# CONNECTORS.net
KiCad netlist of a schematic drawn in Altium Designer
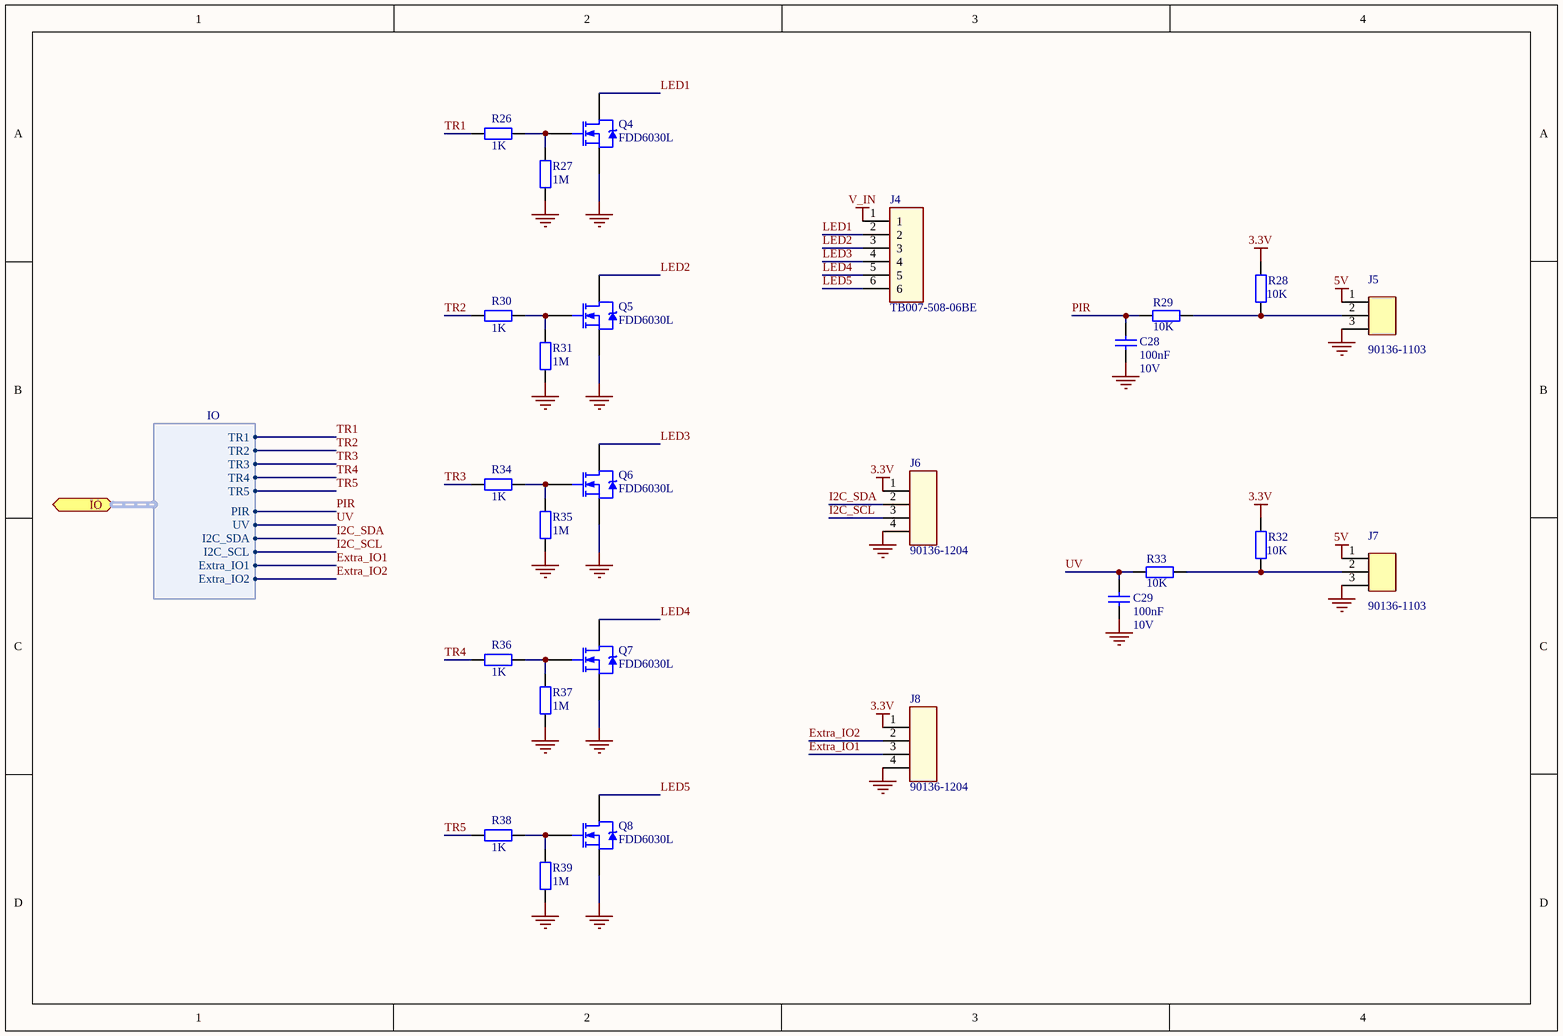
[diagram p0: CONNECTORS.SchDoc]

(export (version "E")
  (design (tool "Eeschema 10.0.6"))
  (components
    (comp (ref "C28")
      (value "Capacitor")
      (footprint "CAPC1608N")
      (fields
        (field (name "PART NUMBER") "CAP-000000005")
        (field (name "VALUE 1") "100nF")
        (field (name "VALUE 2") "10V")
      )
      (libsource (lib "ESP32-Relay-Module") (part "Capacitor"))
    )
    (comp (ref "C29")
      (value "Capacitor")
      (footprint "CAPC1608N")
      (fields
        (field (name "PART NUMBER") "CAP-000000005")
        (field (name "VALUE 1") "100nF")
        (field (name "VALUE 2") "10V")
      )
      (libsource (lib "ESP32-Relay-Module") (part "Capacitor"))
    )
    (comp (ref "J4")
      (value "TB007-508-06BE")
      (footprint "HDR1X6")
      (fields (field (name "PART NUMBER") "CON-000000007"))
      (libsource (lib "ESP32-Relay-Module") (part "Header 1X6"))
    )
    (comp (ref "J5")
      (value "90136-1103")
      (footprint "HDR1X3")
      (fields (field (name "PART NUMBER") "CON-000000003"))
      (libsource (lib "ESP32-Relay-Module") (part "Header 1X3"))
    )
    (comp (ref "J6")
      (value "90136-1204")
      (footprint "HDR1X4")
      (fields (field (name "PART NUMBER") "CON-000000004"))
      (libsource (lib "ESP32-Relay-Module") (part "Header 1X4"))
    )
    (comp (ref "J7")
      (value "90136-1103")
      (footprint "HDR1X3")
      (fields (field (name "PART NUMBER") "CON-000000003"))
      (libsource (lib "ESP32-Relay-Module") (part "Header 1X3"))
    )
    (comp (ref "J8")
      (value "90136-1204")
      (footprint "HDR1X4")
      (fields (field (name "PART NUMBER") "CON-000000004"))
      (libsource (lib "ESP32-Relay-Module") (part "Header 1X4"))
    )
    (comp (ref "Q4")
      (value "FDD6030L")
      (footprint "TO-252-3")
      (fields (field (name "PART NUMBER") "TRM-000000001"))
      (libsource (lib "ESP32-Relay-Module") (part "MOSFET-N-1"))
    )
    (comp (ref "Q5")
      (value "FDD6030L")
      (footprint "TO-252-3")
      (fields (field (name "PART NUMBER") "TRM-000000001"))
      (libsource (lib "ESP32-Relay-Module") (part "MOSFET-N-1"))
    )
    (comp (ref "Q6")
      (value "FDD6030L")
      (footprint "TO-252-3")
      (fields (field (name "PART NUMBER") "TRM-000000001"))
      (libsource (lib "ESP32-Relay-Module") (part "MOSFET-N-1"))
    )
    (comp (ref "Q7")
      (value "FDD6030L")
      (footprint "TO-252-3")
      (fields (field (name "PART NUMBER") "TRM-000000001"))
      (libsource (lib "ESP32-Relay-Module") (part "MOSFET-N-1"))
    )
    (comp (ref "Q8")
      (value "FDD6030L")
      (footprint "TO-252-3")
      (fields (field (name "PART NUMBER") "TRM-000000001"))
      (libsource (lib "ESP32-Relay-Module") (part "MOSFET-N-1"))
    )
    (comp (ref "R26")
      (value "Resistor")
      (footprint "RESC1608N")
      (fields (field (name "PART NUMBER") "RES-000000006") (field (name "VALUE 1") "1K"))
      (libsource (lib "") (part "Resistor_1"))
    )
    (comp (ref "R27")
      (value "Resistor")
      (footprint "RESC1608N")
      (fields (field (name "PART NUMBER") "RES-000000010") (field (name "VALUE 1") "1M"))
      (libsource (lib "ESP32-Relay-Module") (part "Resistor"))
    )
    (comp (ref "R28")
      (value "Resistor")
      (footprint "RESC1608N")
      (fields (field (name "PART NUMBER") "RES-000000001") (field (name "VALUE 1") "10K"))
      (libsource (lib "ESP32-Relay-Module") (part "Resistor"))
    )
    (comp (ref "R29")
      (value "Resistor")
      (footprint "RESC1608N")
      (fields (field (name "PART NUMBER") "RES-000000001") (field (name "VALUE 1") "10K"))
      (libsource (lib "") (part "Resistor_2"))
    )
    (comp (ref "R30")
      (value "Resistor")
      (footprint "RESC1608N")
      (fields (field (name "PART NUMBER") "RES-000000006") (field (name "VALUE 1") "1K"))
      (libsource (lib "") (part "Resistor_1"))
    )
    (comp (ref "R31")
      (value "Resistor")
      (footprint "RESC1608N")
      (fields (field (name "PART NUMBER") "RES-000000010") (field (name "VALUE 1") "1M"))
      (libsource (lib "ESP32-Relay-Module") (part "Resistor"))
    )
    (comp (ref "R32")
      (value "Resistor")
      (footprint "RESC1608N")
      (fields (field (name "PART NUMBER") "RES-000000001") (field (name "VALUE 1") "10K"))
      (libsource (lib "ESP32-Relay-Module") (part "Resistor"))
    )
    (comp (ref "R33")
      (value "Resistor")
      (footprint "RESC1608N")
      (fields (field (name "PART NUMBER") "RES-000000001") (field (name "VALUE 1") "10K"))
      (libsource (lib "") (part "Resistor_2"))
    )
    (comp (ref "R34")
      (value "Resistor")
      (footprint "RESC1608N")
      (fields (field (name "PART NUMBER") "RES-000000006") (field (name "VALUE 1") "1K"))
      (libsource (lib "") (part "Resistor_1"))
    )
    (comp (ref "R35")
      (value "Resistor")
      (footprint "RESC1608N")
      (fields (field (name "PART NUMBER") "RES-000000010") (field (name "VALUE 1") "1M"))
      (libsource (lib "ESP32-Relay-Module") (part "Resistor"))
    )
    (comp (ref "R36")
      (value "Resistor")
      (footprint "RESC1608N")
      (fields (field (name "PART NUMBER") "RES-000000006") (field (name "VALUE 1") "1K"))
      (libsource (lib "") (part "Resistor_1"))
    )
    (comp (ref "R37")
      (value "Resistor")
      (footprint "RESC1608N")
      (fields (field (name "PART NUMBER") "RES-000000010") (field (name "VALUE 1") "1M"))
      (libsource (lib "ESP32-Relay-Module") (part "Resistor"))
    )
    (comp (ref "R38")
      (value "Resistor")
      (footprint "RESC1608N")
      (fields (field (name "PART NUMBER") "RES-000000006") (field (name "VALUE 1") "1K"))
      (libsource (lib "") (part "Resistor_1"))
    )
    (comp (ref "R39")
      (value "Resistor")
      (footprint "RESC1608N")
      (fields (field (name "PART NUMBER") "RES-000000010") (field (name "VALUE 1") "1M"))
      (libsource (lib "ESP32-Relay-Module") (part "Resistor"))
    )
  )
  (nets
    (net (code "2") (name "/Extra_IO1") (class "Default")
      (node (ref "J8") (pin "3") (pinfunction "3_3") (pintype "passive"))
    )
    (net (code "3") (name "/Extra_IO2") (class "Default")
      (node (ref "J8") (pin "2") (pinfunction "2_2") (pintype "passive"))
    )
    (net (code "4") (name "/I2C_SCL") (class "Default")
      (node (ref "J6") (pin "3") (pinfunction "3_3") (pintype "passive"))
    )
    (net (code "5") (name "/I2C_SDA") (class "Default")
      (node (ref "J6") (pin "2") (pinfunction "2_2") (pintype "passive"))
    )
    (net (code "6") (name "/LED1") (class "Default")
      (node (ref "J4") (pin "2") (pinfunction "2_2") (pintype "passive"))
      (node (ref "Q4") (pin "4") (pinfunction "D_4") (pintype "passive"))
    )
    (net (code "7") (name "/LED2") (class "Default")
      (node (ref "J4") (pin "3") (pinfunction "3_3") (pintype "passive"))
      (node (ref "Q5") (pin "4") (pinfunction "D_4") (pintype "passive"))
    )
    (net (code "8") (name "/LED3") (class "Default")
      (node (ref "J4") (pin "4") (pinfunction "4_4") (pintype "passive"))
      (node (ref "Q6") (pin "4") (pinfunction "D_4") (pintype "passive"))
    )
    (net (code "9") (name "/LED4") (class "Default")
      (node (ref "J4") (pin "5") (pinfunction "5_5") (pintype "passive"))
      (node (ref "Q7") (pin "4") (pinfunction "D_4") (pintype "passive"))
    )
    (net (code "10") (name "/LED5") (class "Default")
      (node (ref "J4") (pin "6") (pinfunction "6_6") (pintype "passive"))
      (node (ref "Q8") (pin "4") (pinfunction "D_4") (pintype "passive"))
    )
    (net (code "11") (name "/PIR") (class "Default")
      (node (ref "C28") (pin "2") (pinfunction "2_2") (pintype "passive"))
      (node (ref "R29") (pin "2") (pinfunction "2_2") (pintype "passive"))
    )
    (net (code "12") (name "/TR1") (class "Default")
      (node (ref "R26") (pin "1") (pinfunction "1_1") (pintype "passive"))
    )
    (net (code "13") (name "/TR2") (class "Default")
      (node (ref "R30") (pin "1") (pinfunction "1_1") (pintype "passive"))
    )
    (net (code "14") (name "/TR3") (class "Default")
      (node (ref "R34") (pin "1") (pinfunction "1_1") (pintype "passive"))
    )
    (net (code "15") (name "/TR4") (class "Default")
      (node (ref "R36") (pin "1") (pinfunction "1_1") (pintype "passive"))
    )
    (net (code "16") (name "/TR5") (class "Default")
      (node (ref "R38") (pin "1") (pinfunction "1_1") (pintype "passive"))
    )
    (net (code "17") (name "/UV") (class "Default")
      (node (ref "C29") (pin "2") (pinfunction "2_2") (pintype "passive"))
      (node (ref "R33") (pin "2") (pinfunction "2_2") (pintype "passive"))
    )
    (net (code "19") (name "3.3V") (class "Default")
      (node (ref "J6") (pin "1") (pinfunction "1_1") (pintype "passive"))
      (node (ref "J8") (pin "1") (pinfunction "1_1") (pintype "passive"))
      (node (ref "R28") (pin "2") (pinfunction "2_2") (pintype "passive"))
      (node (ref "R32") (pin "2") (pinfunction "2_2") (pintype "passive"))
    )
    (net (code "20") (name "5V") (class "Default")
      (node (ref "J5") (pin "1") (pinfunction "1_1") (pintype "passive"))
      (node (ref "J7") (pin "1") (pinfunction "1_1") (pintype "passive"))
    )
    (net (code "21") (name "GND") (class "Default")
      (node (ref "C28") (pin "1") (pinfunction "1_1") (pintype "passive"))
      (node (ref "C29") (pin "1") (pinfunction "1_1") (pintype "passive"))
      (node (ref "J5") (pin "3") (pinfunction "3_3") (pintype "passive"))
      (node (ref "J6") (pin "4") (pinfunction "4_4") (pintype "passive"))
      (node (ref "J7") (pin "3") (pinfunction "3_3") (pintype "passive"))
      (node (ref "J8") (pin "4") (pinfunction "4_4") (pintype "passive"))
      (node (ref "Q4") (pin "3") (pinfunction "S_3") (pintype "passive"))
      (node (ref "Q5") (pin "3") (pinfunction "S_3") (pintype "passive"))
      (node (ref "Q6") (pin "3") (pinfunction "S_3") (pintype "passive"))
      (node (ref "Q7") (pin "3") (pinfunction "S_3") (pintype "passive"))
      (node (ref "Q8") (pin "3") (pinfunction "S_3") (pintype "passive"))
      (node (ref "R27") (pin "1") (pinfunction "1_1") (pintype "passive"))
      (node (ref "R31") (pin "1") (pinfunction "1_1") (pintype "passive"))
      (node (ref "R35") (pin "1") (pinfunction "1_1") (pintype "passive"))
      (node (ref "R37") (pin "1") (pinfunction "1_1") (pintype "passive"))
      (node (ref "R39") (pin "1") (pinfunction "1_1") (pintype "passive"))
    )
    (net (code "22") (name "Net-(J5-Pad2)") (class "Default")
      (node (ref "J5") (pin "2") (pinfunction "2_2") (pintype "passive"))
      (node (ref "R28") (pin "1") (pinfunction "1_1") (pintype "passive"))
      (node (ref "R29") (pin "1") (pinfunction "1_1") (pintype "passive"))
    )
    (net (code "23") (name "Net-(J7-Pad2)") (class "Default")
      (node (ref "J7") (pin "2") (pinfunction "2_2") (pintype "passive"))
      (node (ref "R32") (pin "1") (pinfunction "1_1") (pintype "passive"))
      (node (ref "R33") (pin "1") (pinfunction "1_1") (pintype "passive"))
    )
    (net (code "24") (name "Net-(Q4-G)") (class "Default")
      (node (ref "Q4") (pin "1") (pinfunction "G_1") (pintype "passive"))
      (node (ref "R26") (pin "2") (pinfunction "2_2") (pintype "passive"))
      (node (ref "R27") (pin "2") (pinfunction "2_2") (pintype "passive"))
    )
    (net (code "25") (name "Net-(Q5-G)") (class "Default")
      (node (ref "Q5") (pin "1") (pinfunction "G_1") (pintype "passive"))
      (node (ref "R30") (pin "2") (pinfunction "2_2") (pintype "passive"))
      (node (ref "R31") (pin "2") (pinfunction "2_2") (pintype "passive"))
    )
    (net (code "26") (name "Net-(Q6-G)") (class "Default")
      (node (ref "Q6") (pin "1") (pinfunction "G_1") (pintype "passive"))
      (node (ref "R34") (pin "2") (pinfunction "2_2") (pintype "passive"))
      (node (ref "R35") (pin "2") (pinfunction "2_2") (pintype "passive"))
    )
    (net (code "27") (name "Net-(Q7-G)") (class "Default")
      (node (ref "Q7") (pin "1") (pinfunction "G_1") (pintype "passive"))
      (node (ref "R36") (pin "2") (pinfunction "2_2") (pintype "passive"))
      (node (ref "R37") (pin "2") (pinfunction "2_2") (pintype "passive"))
    )
    (net (code "28") (name "Net-(Q8-G)") (class "Default")
      (node (ref "Q8") (pin "1") (pinfunction "G_1") (pintype "passive"))
      (node (ref "R38") (pin "2") (pinfunction "2_2") (pintype "passive"))
      (node (ref "R39") (pin "2") (pinfunction "2_2") (pintype "passive"))
    )
    (net (code "29") (name "V_IN") (class "Default")
      (node (ref "J4") (pin "1") (pinfunction "1_1") (pintype "passive"))
    )
  )
)
